# dual_control_board.net
KiCad netlist of a schematic drawn in EAGLE
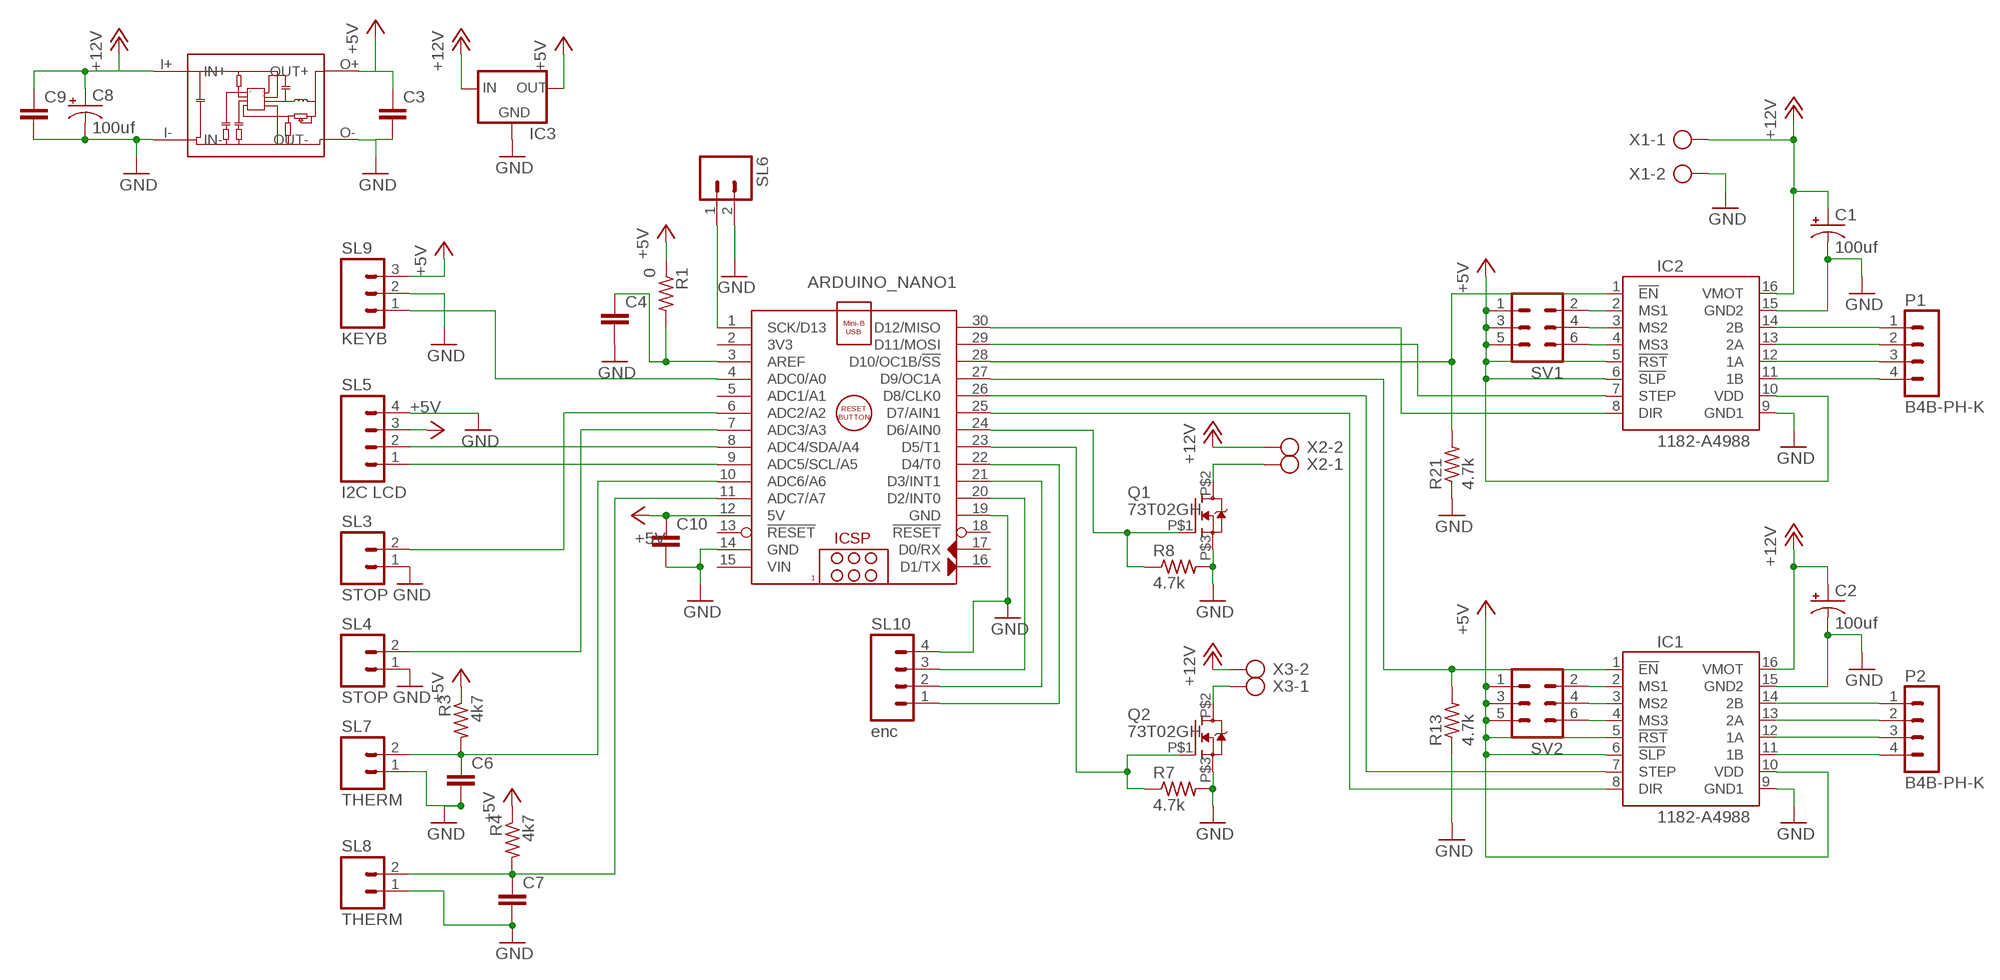
[diagram p0: schematic, sheet 1]

(export (version "E")
  (design (tool "Eeschema 10.0.6"))
  (components
    (comp (ref "ARDUINO_NANO1")
      (value "ARDUINO_NANO")
      (footprint "eagle-import:ARDUINO_NANO")
      (libsource (lib "eagle-import") (part "ARDUINO_NANO"))
    )
    (comp (ref "C1")
      (value "100uf")
      (footprint "eagle-import:E3,5-8")
      (libsource (lib "eagle-import") (part "CPOL-USE3.5-8"))
    )
    (comp (ref "C2")
      (value "100uf")
      (footprint "eagle-import:E3,5-8")
      (libsource (lib "eagle-import") (part "CPOL-USE3.5-8"))
    )
    (comp (ref "C3")
      (value "C-EU050-024X044")
      (footprint "eagle-import:C050-024X044")
      (libsource (lib "eagle-import") (part "C-EU050-024X044"))
    )
    (comp (ref "C4")
      (value "C-EU050-024X044")
      (footprint "eagle-import:C050-024X044")
      (libsource (lib "eagle-import") (part "C-EU050-024X044"))
    )
    (comp (ref "C6")
      (value "C-EU050-024X044")
      (footprint "eagle-import:C050-024X044")
      (libsource (lib "eagle-import") (part "C-EU050-024X044"))
    )
    (comp (ref "C7")
      (value "C-EU050-024X044")
      (footprint "eagle-import:C050-024X044")
      (libsource (lib "eagle-import") (part "C-EU050-024X044"))
    )
    (comp (ref "C8")
      (value "100uf")
      (footprint "eagle-import:E3,5-8")
      (libsource (lib "eagle-import") (part "CPOL-USE3.5-8"))
    )
    (comp (ref "C9")
      (value "C-EU050-024X044")
      (footprint "eagle-import:C050-024X044")
      (libsource (lib "eagle-import") (part "C-EU050-024X044"))
    )
    (comp (ref "C10")
      (value "C-EU050-024X044")
      (footprint "eagle-import:C050-024X044")
      (libsource (lib "eagle-import") (part "C-EU050-024X044"))
    )
    (comp (ref "IC1")
      (value "1182-A4988")
      (footprint "eagle-import:A4988")
      (libsource (lib "eagle-import") (part "1182-A4988"))
    )
    (comp (ref "IC2")
      (value "1182-A4988")
      (footprint "eagle-import:A4988")
      (libsource (lib "eagle-import") (part "1182-A4988"))
    )
    (comp (ref "IC3")
      (value "78XXL")
      (footprint "eagle-import:78XXL")
      (libsource (lib "eagle-import") (part "78XXL"))
    )
    (comp (ref "P1")
      (value "B4B-PH-K")
      (footprint "eagle-import:B4B-PH-K")
      (libsource (lib "eagle-import") (part "B4B-PH-K"))
    )
    (comp (ref "P2")
      (value "B4B-PH-K")
      (footprint "eagle-import:B4B-PH-K")
      (libsource (lib "eagle-import") (part "B4B-PH-K"))
    )
    (comp (ref "Q1")
      (value "73T02GH")
      (footprint "eagle-import:TO252")
      (libsource (lib "eagle-import") (part "73T02GH"))
    )
    (comp (ref "Q2")
      (value "73T02GH")
      (footprint "eagle-import:TO252")
      (libsource (lib "eagle-import") (part "73T02GH"))
    )
    (comp (ref "R1")
      (value "0")
      (footprint "eagle-import:0204_5")
      (libsource (lib "eagle-import") (part "R-US_0204/5"))
    )
    (comp (ref "R3")
      (value "4k7")
      (footprint "eagle-import:0204_5")
      (libsource (lib "eagle-import") (part "R-US_0204/5"))
    )
    (comp (ref "R4")
      (value "4k7")
      (footprint "eagle-import:0204_5")
      (libsource (lib "eagle-import") (part "R-US_0204/5"))
    )
    (comp (ref "R7")
      (value "4.7k")
      (footprint "eagle-import:0204_5")
      (libsource (lib "eagle-import") (part "R-US_0204/5"))
    )
    (comp (ref "R8")
      (value "4.7k")
      (footprint "eagle-import:0204_5")
      (libsource (lib "eagle-import") (part "R-US_0204/5"))
    )
    (comp (ref "R13")
      (value "4.7k")
      (footprint "eagle-import:0204_5")
      (libsource (lib "eagle-import") (part "R-US_0204/5"))
    )
    (comp (ref "R21")
      (value "4.7k")
      (footprint "eagle-import:0204_5")
      (libsource (lib "eagle-import") (part "R-US_0204/5"))
    )
    (comp (ref "SL3")
      (value "STOP")
      (footprint "eagle-import:02P")
      (libsource (lib "eagle-import") (part "M02"))
    )
    (comp (ref "SL4")
      (value "STOP")
      (footprint "eagle-import:02P")
      (libsource (lib "eagle-import") (part "M02"))
    )
    (comp (ref "SL5")
      (value "I2C LCD")
      (footprint "eagle-import:04P")
      (libsource (lib "eagle-import") (part "M04"))
    )
    (comp (ref "SL6")
      (value "M02")
      (footprint "eagle-import:02P")
      (libsource (lib "eagle-import") (part "M02"))
    )
    (comp (ref "SL7")
      (value "THERM")
      (footprint "eagle-import:02P")
      (libsource (lib "eagle-import") (part "M02"))
    )
    (comp (ref "SL8")
      (value "THERM")
      (footprint "eagle-import:02P")
      (libsource (lib "eagle-import") (part "M02"))
    )
    (comp (ref "SL9")
      (value "KEYB")
      (footprint "eagle-import:03P")
      (libsource (lib "eagle-import") (part "M03"))
    )
    (comp (ref "SL10")
      (value "enc")
      (footprint "eagle-import:04P")
      (libsource (lib "eagle-import") (part "M04"))
    )
    (comp (ref "SV1")
      (value "MA03-2")
      (footprint "eagle-import:MA03-2")
      (libsource (lib "eagle-import") (part "MA03-2"))
    )
    (comp (ref "SV2")
      (value "MA03-2")
      (footprint "eagle-import:MA03-2")
      (libsource (lib "eagle-import") (part "MA03-2"))
    )
    (comp (ref "U$1")
      (value "MINI360")
      (footprint "eagle-import:MINI360")
      (libsource (lib "eagle-import") (part "MINI360"))
    )
    (comp (ref "X1")
      (value "AK500/2")
      (footprint "eagle-import:AK500_2")
      (libsource (lib "eagle-import") (part "AK500/2"))
    )
    (comp (ref "X2")
      (value "AK500/2")
      (footprint "eagle-import:AK500_2")
      (libsource (lib "eagle-import") (part "AK500/2"))
    )
    (comp (ref "X3")
      (value "AK500/2")
      (footprint "eagle-import:AK500_2")
      (libsource (lib "eagle-import") (part "AK500/2"))
    )
  )
  (nets
    (net (code "1") (name "+5V") (class "Default")
      (node (ref "ARDUINO_NANO1") (pin "12") (pinfunction "5V_12") (pintype "power_in"))
      (node (ref "C10") (pin "1") (pinfunction "1_1") (pintype "passive"))
      (node (ref "C3") (pin "1") (pinfunction "1_1") (pintype "passive"))
      (node (ref "IC1") (pin "10") (pinfunction "VDD_10") (pintype "power_in"))
      (node (ref "IC1") (pin "5") (pinfunction "~{RST}_5") (pintype "passive"))
      (node (ref "IC1") (pin "6") (pinfunction "~{SLP}_6") (pintype "passive"))
      (node (ref "IC2") (pin "10") (pinfunction "VDD_10") (pintype "power_in"))
      (node (ref "IC2") (pin "5") (pinfunction "~{RST}_5") (pintype "passive"))
      (node (ref "IC2") (pin "6") (pinfunction "~{SLP}_6") (pintype "passive"))
      (node (ref "IC3") (pin "OUT") (pinfunction "OUT_OUT") (pintype "passive"))
      (node (ref "R1") (pin "1") (pinfunction "1_1") (pintype "passive"))
      (node (ref "R3") (pin "1") (pinfunction "1_1") (pintype "passive"))
      (node (ref "R4") (pin "1") (pinfunction "1_1") (pintype "passive"))
      (node (ref "SL5") (pin "3") (pinfunction "3_3") (pintype "passive"))
      (node (ref "SL9") (pin "3") (pinfunction "3_3") (pintype "passive"))
      (node (ref "SV1") (pin "1") (pinfunction "1_1") (pintype "passive"))
      (node (ref "SV1") (pin "3") (pinfunction "3_3") (pintype "passive"))
      (node (ref "SV1") (pin "5") (pinfunction "5_5") (pintype "passive"))
      (node (ref "SV2") (pin "1") (pinfunction "1_1") (pintype "passive"))
      (node (ref "SV2") (pin "3") (pinfunction "3_3") (pintype "passive"))
      (node (ref "SV2") (pin "5") (pinfunction "5_5") (pintype "passive"))
      (node (ref "U$1") (pin "O+") (pinfunction "OUT+_O+") (pintype "bidirectional"))
    )
    (net (code "2") (name "+12V") (class "Default")
      (node (ref "C1") (pin "+") (pinfunction "+_+") (pintype "passive"))
      (node (ref "C2") (pin "+") (pinfunction "+_+") (pintype "passive"))
      (node (ref "C8") (pin "+") (pinfunction "+_+") (pintype "passive"))
      (node (ref "C9") (pin "1") (pinfunction "1_1") (pintype "passive"))
      (node (ref "IC1") (pin "16") (pinfunction "VMOT_16") (pintype "power_in"))
      (node (ref "IC2") (pin "16") (pinfunction "VMOT_16") (pintype "power_in"))
      (node (ref "IC3") (pin "IN") (pinfunction "IN_IN") (pintype "input"))
      (node (ref "U$1") (pin "I+") (pinfunction "IN+_I+") (pintype "bidirectional"))
      (node (ref "X1") (pin "1") (pinfunction "KL_1") (pintype "passive"))
      (node (ref "X2") (pin "2") (pinfunction "KL_2") (pintype "passive"))
      (node (ref "X3") (pin "2") (pinfunction "KL_2") (pintype "passive"))
    )
    (net (code "3") (name "/VIN") (class "Default")
      (node (ref "ARDUINO_NANO1") (pin "15") (pinfunction "VIN_15") (pintype "power_in"))
    )
    (net (code "4") (name "GND") (class "Default")
      (node (ref "ARDUINO_NANO1") (pin "14") (pinfunction "GND_14") (pintype "power_in"))
      (node (ref "ARDUINO_NANO1") (pin "19") (pinfunction "GND_19") (pintype "power_in"))
      (node (ref "C1") (pin "-") (pinfunction "-_-") (pintype "passive"))
      (node (ref "C10") (pin "2") (pinfunction "2_2") (pintype "passive"))
      (node (ref "C2") (pin "-") (pinfunction "-_-") (pintype "passive"))
      (node (ref "C3") (pin "2") (pinfunction "2_2") (pintype "passive"))
      (node (ref "C4") (pin "2") (pinfunction "2_2") (pintype "passive"))
      (node (ref "C6") (pin "2") (pinfunction "2_2") (pintype "passive"))
      (node (ref "C7") (pin "2") (pinfunction "2_2") (pintype "passive"))
      (node (ref "C8") (pin "-") (pinfunction "-_-") (pintype "passive"))
      (node (ref "C9") (pin "2") (pinfunction "2_2") (pintype "passive"))
      (node (ref "IC1") (pin "15") (pinfunction "GND2_15") (pintype "power_in"))
      (node (ref "IC1") (pin "9") (pinfunction "GND1_9") (pintype "power_in"))
      (node (ref "IC2") (pin "15") (pinfunction "GND2_15") (pintype "power_in"))
      (node (ref "IC2") (pin "9") (pinfunction "GND1_9") (pintype "power_in"))
      (node (ref "IC3") (pin "GND") (pinfunction "GND_GND") (pintype "input"))
      (node (ref "Q1") (pin "P$3") (pinfunction "S_P$3") (pintype "passive"))
      (node (ref "Q2") (pin "P$3") (pinfunction "S_P$3") (pintype "passive"))
      (node (ref "R13") (pin "1") (pinfunction "1_1") (pintype "passive"))
      (node (ref "R21") (pin "1") (pinfunction "1_1") (pintype "passive"))
      (node (ref "R7") (pin "2") (pinfunction "2_2") (pintype "passive"))
      (node (ref "R8") (pin "2") (pinfunction "2_2") (pintype "passive"))
      (node (ref "SL10") (pin "4") (pinfunction "4_4") (pintype "passive"))
      (node (ref "SL3") (pin "1") (pinfunction "1_1") (pintype "passive"))
      (node (ref "SL4") (pin "1") (pinfunction "1_1") (pintype "passive"))
      (node (ref "SL5") (pin "4") (pinfunction "4_4") (pintype "passive"))
      (node (ref "SL6") (pin "2") (pinfunction "2_2") (pintype "passive"))
      (node (ref "SL7") (pin "1") (pinfunction "1_1") (pintype "passive"))
      (node (ref "SL8") (pin "1") (pinfunction "1_1") (pintype "passive"))
      (node (ref "SL9") (pin "2") (pinfunction "2_2") (pintype "passive"))
      (node (ref "U$1") (pin "I-") (pinfunction "IN-_I-") (pintype "bidirectional"))
      (node (ref "U$1") (pin "O-") (pinfunction "OUT-_O-") (pintype "bidirectional"))
      (node (ref "X1") (pin "2") (pinfunction "KL_2") (pintype "passive"))
    )
    (net (code "5") (name "Net-(ARDUINO_NANO1-ADC0{slash}A0)") (class "Default")
      (node (ref "ARDUINO_NANO1") (pin "4") (pinfunction "ADC0/A0_4") (pintype "bidirectional"))
      (node (ref "SL9") (pin "1") (pinfunction "1_1") (pintype "passive"))
    )
    (net (code "6") (name "Net-(ARDUINO_NANO1-ADC2{slash}A2)") (class "Default")
      (node (ref "ARDUINO_NANO1") (pin "6") (pinfunction "ADC2/A2_6") (pintype "bidirectional"))
      (node (ref "SL3") (pin "2") (pinfunction "2_2") (pintype "passive"))
    )
    (net (code "7") (name "Net-(ARDUINO_NANO1-ADC3{slash}A3)") (class "Default")
      (node (ref "ARDUINO_NANO1") (pin "7") (pinfunction "ADC3/A3_7") (pintype "bidirectional"))
      (node (ref "SL4") (pin "2") (pinfunction "2_2") (pintype "passive"))
    )
    (net (code "8") (name "Net-(ARDUINO_NANO1-ADC4{slash}SDA{slash}A4)") (class "Default")
      (node (ref "ARDUINO_NANO1") (pin "8") (pinfunction "ADC4/SDA/A4_8") (pintype "bidirectional"))
      (node (ref "SL5") (pin "2") (pinfunction "2_2") (pintype "passive"))
    )
    (net (code "9") (name "Net-(ARDUINO_NANO1-ADC5{slash}SCL{slash}A5)") (class "Default")
      (node (ref "ARDUINO_NANO1") (pin "9") (pinfunction "ADC5/SCL/A5_9") (pintype "bidirectional"))
      (node (ref "SL5") (pin "1") (pinfunction "1_1") (pintype "passive"))
    )
    (net (code "10") (name "Net-(ARDUINO_NANO1-ADC6{slash}A6)") (class "Default")
      (node (ref "ARDUINO_NANO1") (pin "10") (pinfunction "ADC6/A6_10") (pintype "bidirectional"))
      (node (ref "C6") (pin "1") (pinfunction "1_1") (pintype "passive"))
      (node (ref "R3") (pin "2") (pinfunction "2_2") (pintype "passive"))
      (node (ref "SL7") (pin "2") (pinfunction "2_2") (pintype "passive"))
    )
    (net (code "11") (name "Net-(ARDUINO_NANO1-ADC7{slash}A7)") (class "Default")
      (node (ref "ARDUINO_NANO1") (pin "11") (pinfunction "ADC7/A7_11") (pintype "bidirectional"))
      (node (ref "C7") (pin "1") (pinfunction "1_1") (pintype "passive"))
      (node (ref "R4") (pin "2") (pinfunction "2_2") (pintype "passive"))
      (node (ref "SL8") (pin "2") (pinfunction "2_2") (pintype "passive"))
    )
    (net (code "12") (name "Net-(ARDUINO_NANO1-AREF)") (class "Default")
      (node (ref "ARDUINO_NANO1") (pin "3") (pinfunction "AREF_3") (pintype "input"))
      (node (ref "C4") (pin "1") (pinfunction "1_1") (pintype "passive"))
      (node (ref "R1") (pin "2") (pinfunction "2_2") (pintype "passive"))
    )
    (net (code "13") (name "Net-(ARDUINO_NANO1-D2{slash}INT0)") (class "Default")
      (node (ref "ARDUINO_NANO1") (pin "20") (pinfunction "D2/INT0_20") (pintype "bidirectional"))
      (node (ref "SL10") (pin "3") (pinfunction "3_3") (pintype "passive"))
    )
    (net (code "14") (name "Net-(ARDUINO_NANO1-D3{slash}INT1)") (class "Default")
      (node (ref "ARDUINO_NANO1") (pin "21") (pinfunction "D3/INT1_21") (pintype "bidirectional"))
      (node (ref "SL10") (pin "2") (pinfunction "2_2") (pintype "passive"))
    )
    (net (code "15") (name "Net-(ARDUINO_NANO1-D4{slash}T0)") (class "Default")
      (node (ref "ARDUINO_NANO1") (pin "22") (pinfunction "D4/T0_22") (pintype "bidirectional"))
      (node (ref "SL10") (pin "1") (pinfunction "1_1") (pintype "passive"))
    )
    (net (code "16") (name "Net-(ARDUINO_NANO1-D5{slash}T1)") (class "Default")
      (node (ref "ARDUINO_NANO1") (pin "23") (pinfunction "D5/T1_23") (pintype "bidirectional"))
      (node (ref "Q2") (pin "P$1") (pinfunction "G_P$1") (pintype "passive"))
      (node (ref "R7") (pin "1") (pinfunction "1_1") (pintype "passive"))
    )
    (net (code "17") (name "Net-(ARDUINO_NANO1-D6{slash}AIN0)") (class "Default")
      (node (ref "ARDUINO_NANO1") (pin "24") (pinfunction "D6/AIN0_24") (pintype "bidirectional"))
      (node (ref "Q1") (pin "P$1") (pinfunction "G_P$1") (pintype "passive"))
      (node (ref "R8") (pin "1") (pinfunction "1_1") (pintype "passive"))
    )
    (net (code "18") (name "Net-(ARDUINO_NANO1-D7{slash}AIN1)") (class "Default")
      (node (ref "ARDUINO_NANO1") (pin "25") (pinfunction "D7/AIN1_25") (pintype "bidirectional"))
      (node (ref "IC1") (pin "8") (pinfunction "DIR_8") (pintype "input"))
    )
    (net (code "19") (name "Net-(ARDUINO_NANO1-D8{slash}CLK0)") (class "Default")
      (node (ref "ARDUINO_NANO1") (pin "26") (pinfunction "D8/CLK0_26") (pintype "bidirectional"))
      (node (ref "IC1") (pin "7") (pinfunction "STEP_7") (pintype "input"))
    )
    (net (code "20") (name "Net-(ARDUINO_NANO1-D9{slash}OC1A)") (class "Default")
      (node (ref "ARDUINO_NANO1") (pin "27") (pinfunction "D9/OC1A_27") (pintype "bidirectional"))
      (node (ref "IC1") (pin "1") (pinfunction "~{EN}_1") (pintype "passive"))
      (node (ref "R13") (pin "2") (pinfunction "2_2") (pintype "passive"))
    )
    (net (code "21") (name "Net-(ARDUINO_NANO1-D10{slash}OC1B{slash}~{SS})") (class "Default")
      (node (ref "ARDUINO_NANO1") (pin "28") (pinfunction "D10/OC1B/~{SS}_28") (pintype "bidirectional"))
      (node (ref "IC2") (pin "1") (pinfunction "~{EN}_1") (pintype "passive"))
      (node (ref "R21") (pin "2") (pinfunction "2_2") (pintype "passive"))
    )
    (net (code "22") (name "Net-(ARDUINO_NANO1-D11{slash}MOSI)") (class "Default")
      (node (ref "ARDUINO_NANO1") (pin "29") (pinfunction "D11/MOSI_29") (pintype "bidirectional"))
      (node (ref "IC2") (pin "7") (pinfunction "STEP_7") (pintype "input"))
    )
    (net (code "23") (name "Net-(ARDUINO_NANO1-D12{slash}MISO)") (class "Default")
      (node (ref "ARDUINO_NANO1") (pin "30") (pinfunction "D12/MISO_30") (pintype "bidirectional"))
      (node (ref "IC2") (pin "8") (pinfunction "DIR_8") (pintype "input"))
    )
    (net (code "24") (name "Net-(ARDUINO_NANO1-SCK{slash}D13)") (class "Default")
      (node (ref "ARDUINO_NANO1") (pin "1") (pinfunction "SCK/D13_1") (pintype "bidirectional"))
      (node (ref "SL6") (pin "1") (pinfunction "1_1") (pintype "passive"))
    )
    (net (code "25") (name "Net-(IC1-1A)") (class "Default")
      (node (ref "IC1") (pin "12") (pinfunction "1A_12") (pintype "output"))
      (node (ref "P2") (pin "3") (pinfunction "3_3") (pintype "passive"))
    )
    (net (code "26") (name "Net-(IC1-1B)") (class "Default")
      (node (ref "IC1") (pin "11") (pinfunction "1B_11") (pintype "output"))
      (node (ref "P2") (pin "4") (pinfunction "4_4") (pintype "passive"))
    )
    (net (code "27") (name "Net-(IC1-2A)") (class "Default")
      (node (ref "IC1") (pin "13") (pinfunction "2A_13") (pintype "output"))
      (node (ref "P2") (pin "2") (pinfunction "2_2") (pintype "passive"))
    )
    (net (code "28") (name "Net-(IC1-2B)") (class "Default")
      (node (ref "IC1") (pin "14") (pinfunction "2B_14") (pintype "output"))
      (node (ref "P2") (pin "1") (pinfunction "1_1") (pintype "passive"))
    )
    (net (code "29") (name "Net-(IC1-MS1)") (class "Default")
      (node (ref "IC1") (pin "2") (pinfunction "MS1_2") (pintype "passive"))
      (node (ref "SV2") (pin "2") (pinfunction "2_2") (pintype "passive"))
    )
    (net (code "30") (name "Net-(IC1-MS2)") (class "Default")
      (node (ref "IC1") (pin "3") (pinfunction "MS2_3") (pintype "passive"))
      (node (ref "SV2") (pin "4") (pinfunction "4_4") (pintype "passive"))
    )
    (net (code "31") (name "Net-(IC1-MS3)") (class "Default")
      (node (ref "IC1") (pin "4") (pinfunction "MS3_4") (pintype "passive"))
      (node (ref "SV2") (pin "6") (pinfunction "6_6") (pintype "passive"))
    )
    (net (code "32") (name "Net-(IC2-1A)") (class "Default")
      (node (ref "IC2") (pin "12") (pinfunction "1A_12") (pintype "output"))
      (node (ref "P1") (pin "3") (pinfunction "3_3") (pintype "passive"))
    )
    (net (code "33") (name "Net-(IC2-1B)") (class "Default")
      (node (ref "IC2") (pin "11") (pinfunction "1B_11") (pintype "output"))
      (node (ref "P1") (pin "4") (pinfunction "4_4") (pintype "passive"))
    )
    (net (code "34") (name "Net-(IC2-2A)") (class "Default")
      (node (ref "IC2") (pin "13") (pinfunction "2A_13") (pintype "output"))
      (node (ref "P1") (pin "2") (pinfunction "2_2") (pintype "passive"))
    )
    (net (code "35") (name "Net-(IC2-2B)") (class "Default")
      (node (ref "IC2") (pin "14") (pinfunction "2B_14") (pintype "output"))
      (node (ref "P1") (pin "1") (pinfunction "1_1") (pintype "passive"))
    )
    (net (code "36") (name "Net-(IC2-MS1)") (class "Default")
      (node (ref "IC2") (pin "2") (pinfunction "MS1_2") (pintype "passive"))
      (node (ref "SV1") (pin "2") (pinfunction "2_2") (pintype "passive"))
    )
    (net (code "37") (name "Net-(IC2-MS2)") (class "Default")
      (node (ref "IC2") (pin "3") (pinfunction "MS2_3") (pintype "passive"))
      (node (ref "SV1") (pin "4") (pinfunction "4_4") (pintype "passive"))
    )
    (net (code "38") (name "Net-(IC2-MS3)") (class "Default")
      (node (ref "IC2") (pin "4") (pinfunction "MS3_4") (pintype "passive"))
      (node (ref "SV1") (pin "6") (pinfunction "6_6") (pintype "passive"))
    )
    (net (code "39") (name "Net-(Q1-D)") (class "Default")
      (node (ref "Q1") (pin "P$2") (pinfunction "D_P$2") (pintype "passive"))
      (node (ref "X2") (pin "1") (pinfunction "KL_1") (pintype "passive"))
    )
    (net (code "40") (name "Net-(Q2-D)") (class "Default")
      (node (ref "Q2") (pin "P$2") (pinfunction "D_P$2") (pintype "passive"))
      (node (ref "X3") (pin "1") (pinfunction "KL_1") (pintype "passive"))
    )
    (net (code "41") (name "unconnected-(ARDUINO_NANO1-3V3-Pad2)") (class "Default")
      (node (ref "ARDUINO_NANO1") (pin "2") (pinfunction "3V3_2") (pintype "output"))
    )
    (net (code "42") (name "unconnected-(ARDUINO_NANO1-ADC1{slash}A1-Pad5)") (class "Default")
      (node (ref "ARDUINO_NANO1") (pin "5") (pinfunction "ADC1/A1_5") (pintype "bidirectional"))
    )
    (net (code "43") (name "unconnected-(ARDUINO_NANO1-D0{slash}RX-Pad17)") (class "Default")
      (node (ref "ARDUINO_NANO1") (pin "17") (pinfunction "D0/RX_17") (pintype "bidirectional"))
    )
    (net (code "44") (name "unconnected-(ARDUINO_NANO1-D1{slash}TX-Pad16)") (class "Default")
      (node (ref "ARDUINO_NANO1") (pin "16") (pinfunction "D1/TX_16") (pintype "bidirectional"))
    )
    (net (code "45") (name "unconnected-(ARDUINO_NANO1-~{RESET}-Pad13)") (class "Default")
      (node (ref "ARDUINO_NANO1") (pin "13") (pinfunction "~{RESET}_13") (pintype "input"))
    )
    (net (code "46") (name "unconnected-(ARDUINO_NANO1-~{RESET}-Pad18)") (class "Default")
      (node (ref "ARDUINO_NANO1") (pin "18") (pinfunction "~{RESET}_18") (pintype "input"))
    )
  )
)
